# SCH_Hackcard_2024-05-16.net
KiCad netlist of a schematic drawn in EasyEDA
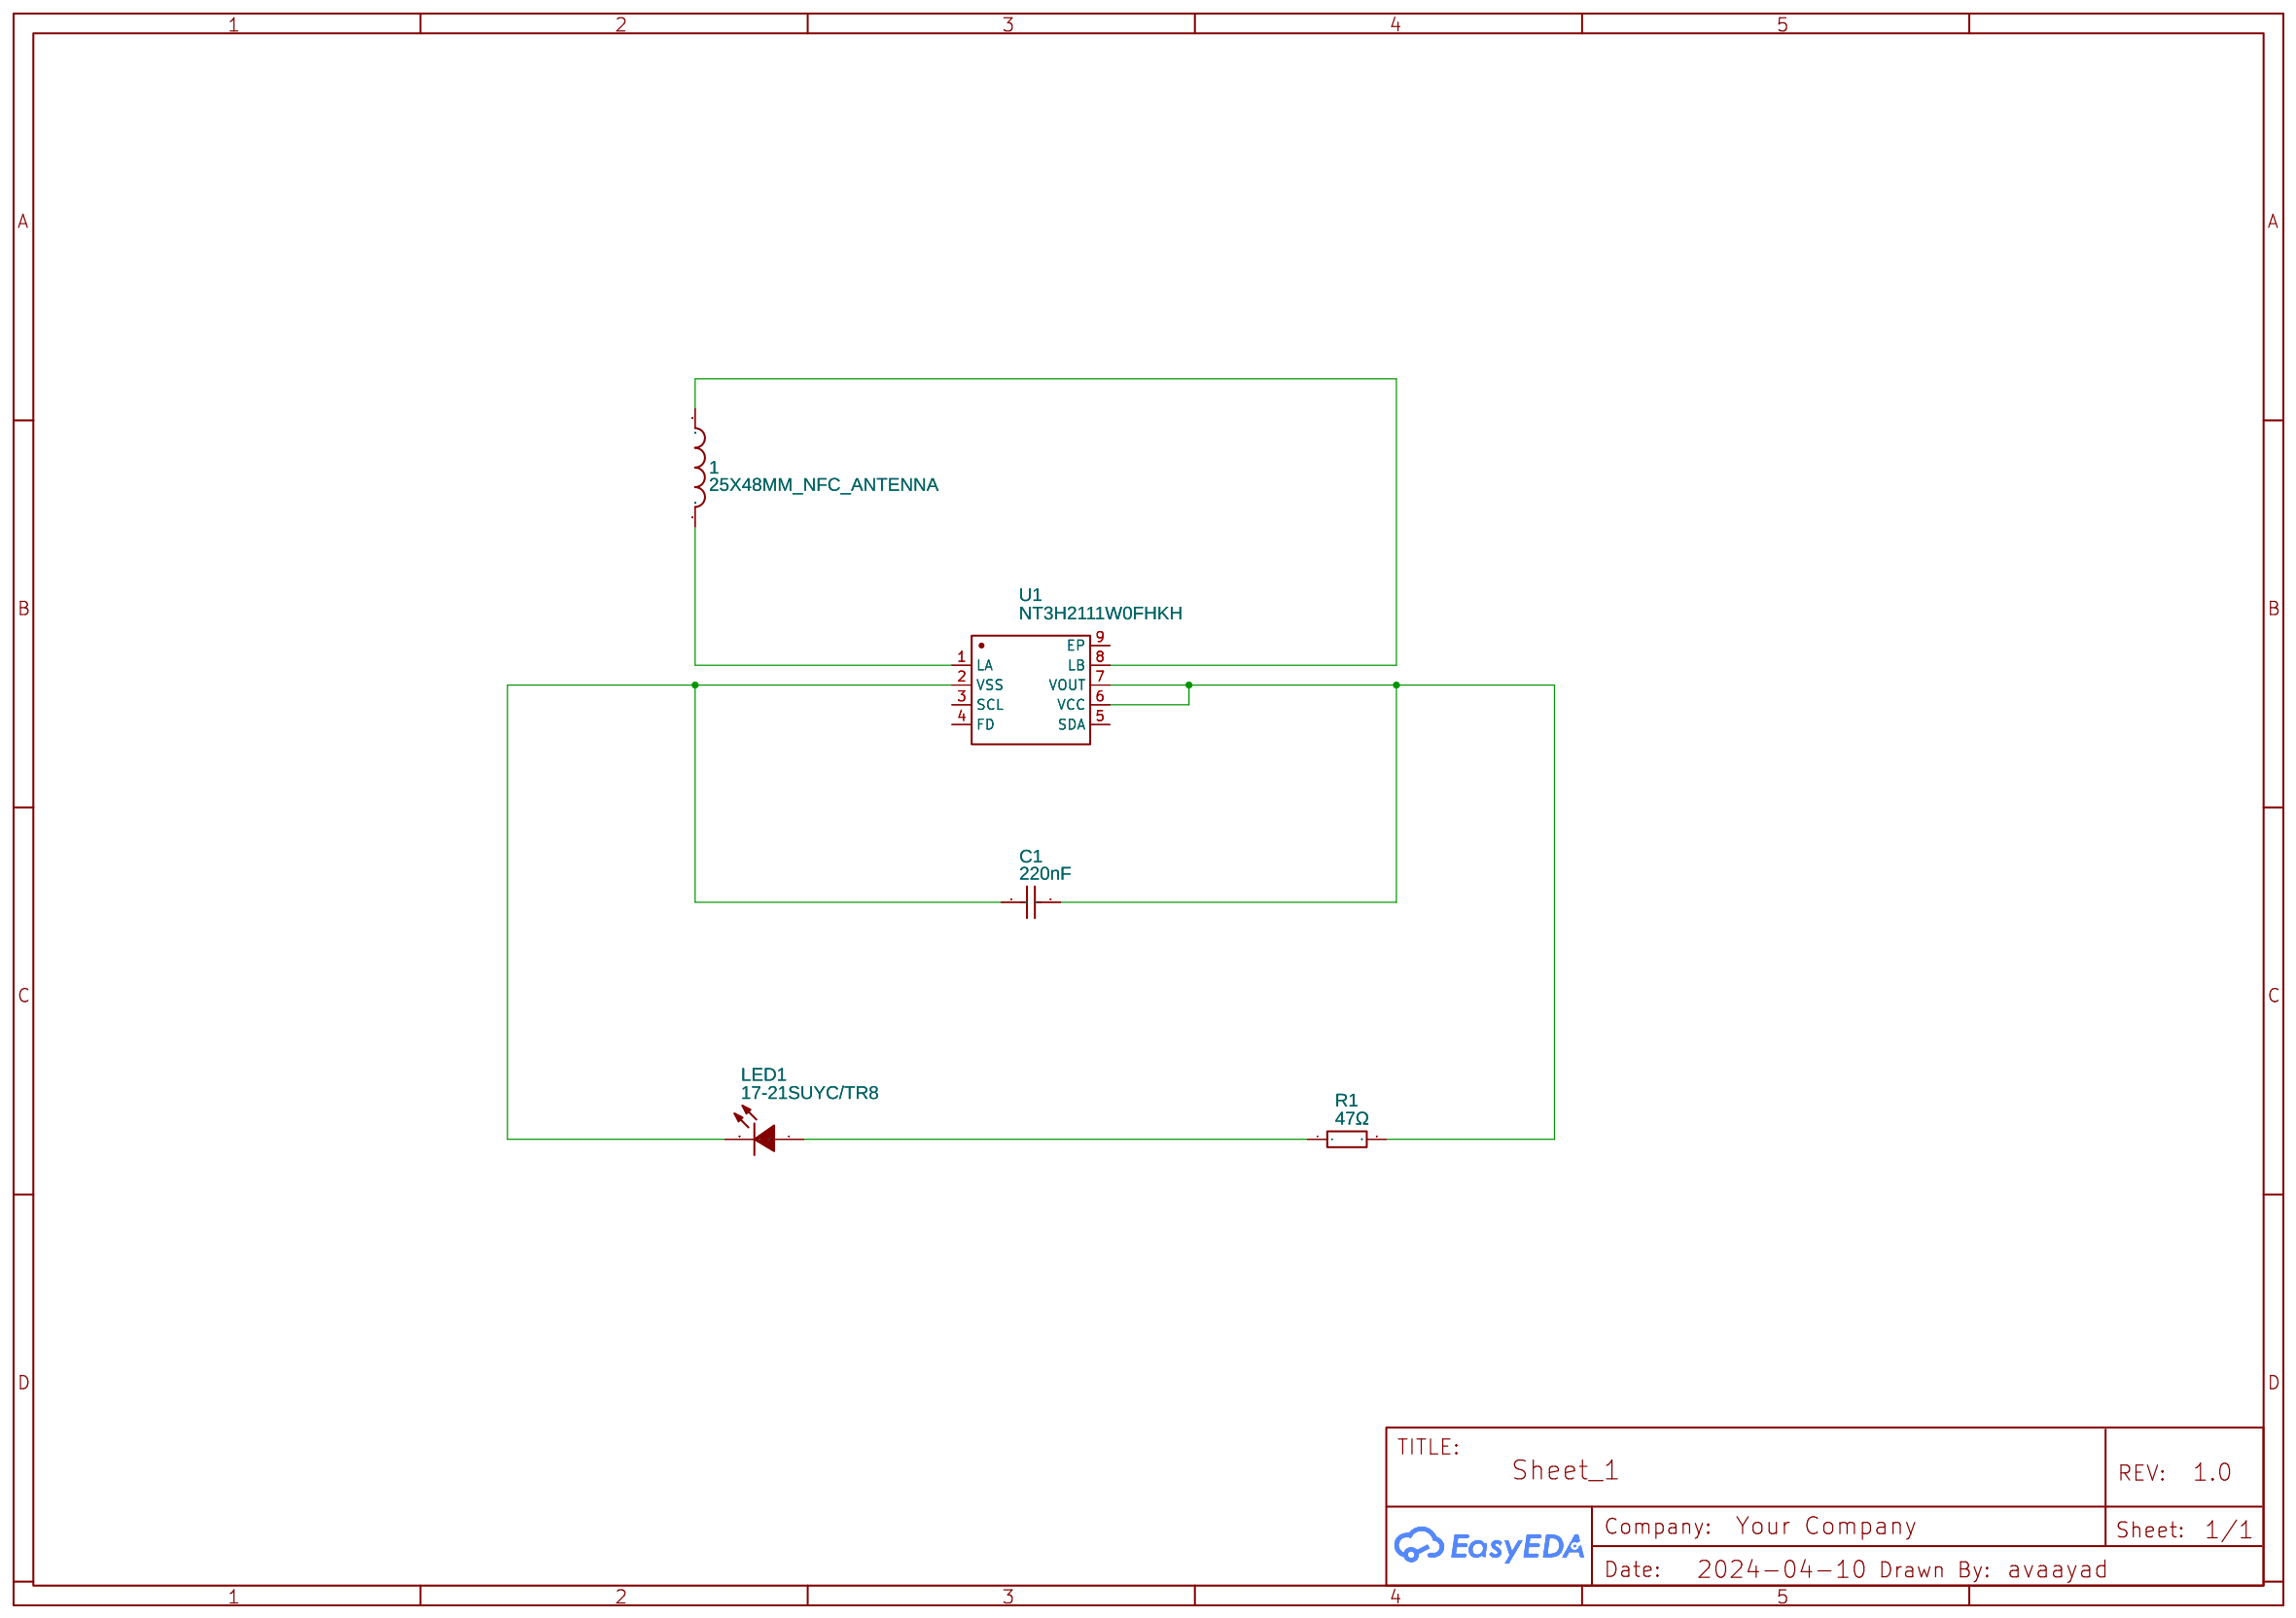
[diagram p0: schematic sheet]

(export (version "E")
  (design (tool "Eeschema 10.0.6"))
  (components
    (comp (ref "1") (value "25X48MM_NFC_ANTENNA") (libsource (lib "") (part "25X48MM_NFC_ANTENNA")))
    (comp (ref "C1")
      (value "220nF")
      (fields
        (field (name "Manufacturer Part") "CL10B224KA8NNNC")
        (field (name "Manufacturer") "SAMSUNG(三星)")
      )
      (libsource (lib "") (part "CL10B224KA8NNNC"))
    )
    (comp (ref "LED1")
      (value "17-21SUYC/TR8")
      (fields (field (name "Manufacturer Part") "KT-0805黄灯") (field (name "Manufacturer") "KENTO"))
      (libsource (lib "") (part "17-21SUYC/TR8"))
    )
    (comp (ref "R1")
      (value "47Ω")
      (fields
        (field (name "Manufacturer Part") "0603WAF470JT5E")
        (field (name "Manufacturer") "UNI-ROYAL(厚声)")
      )
      (libsource (lib "") (part "0603WAF470JT5E"))
    )
    (comp (ref "U1")
      (value "NT3H2111W0FHKH")
      (fields (field (name "Manufacturer") "NXP(恩智浦)"))
      (libsource (lib "") (part "NT3H2111W0FHKH"))
    )
  )
  (nets
    (net (code "1") (name "Net-(LED1-+)") (class "Default")
      (node (ref "LED1") (pin "1") (pinfunction "+_1") (pintype "unspecified"))
      (node (ref "R1") (pin "1") (pinfunction "1_1") (pintype "input"))
    )
    (net (code "2") (name "Net-(LED1--)") (class "Default")
      (node (ref "C1") (pin "1") (pinfunction "1_1") (pintype "input"))
      (node (ref "LED1") (pin "2") (pinfunction "-_2") (pintype "unspecified"))
      (node (ref "U1") (pin "2") (pinfunction "VSS_2") (pintype "unspecified"))
    )
    (net (code "3") (name "Net-(U1-LA)") (class "Default")
      (node (ref "1") (pin "P$2") (pinfunction "P$2_P$2") (pintype "bidirectional"))
      (node (ref "U1") (pin "1") (pinfunction "LA_1") (pintype "unspecified"))
    )
    (net (code "4") (name "Net-(U1-LB)") (class "Default")
      (node (ref "1") (pin "P$1") (pinfunction "P$1_P$1") (pintype "bidirectional"))
      (node (ref "U1") (pin "8") (pinfunction "LB_8") (pintype "unspecified"))
    )
    (net (code "5") (name "Net-(U1-VCC)") (class "Default")
      (node (ref "C1") (pin "2") (pinfunction "2_2") (pintype "input"))
      (node (ref "R1") (pin "2") (pinfunction "2_2") (pintype "input"))
      (node (ref "U1") (pin "6") (pinfunction "VCC_6") (pintype "unspecified"))
      (node (ref "U1") (pin "7") (pinfunction "VOUT_7") (pintype "unspecified"))
    )
    (net (code "6") (name "unconnected-(U1-EP-Pad9)") (class "Default")
      (node (ref "U1") (pin "9") (pinfunction "EP_9") (pintype "unspecified"))
    )
    (net (code "7") (name "unconnected-(U1-FD-Pad4)") (class "Default")
      (node (ref "U1") (pin "4") (pinfunction "FD_4") (pintype "unspecified"))
    )
    (net (code "8") (name "unconnected-(U1-SCL-Pad3)") (class "Default")
      (node (ref "U1") (pin "3") (pinfunction "SCL_3") (pintype "unspecified"))
    )
    (net (code "9") (name "unconnected-(U1-SDA-Pad5)") (class "Default")
      (node (ref "U1") (pin "5") (pinfunction "SDA_5") (pintype "unspecified"))
    )
  )
)
